# pendant2.net
KiCad netlist of a schematic drawn in EAGLE
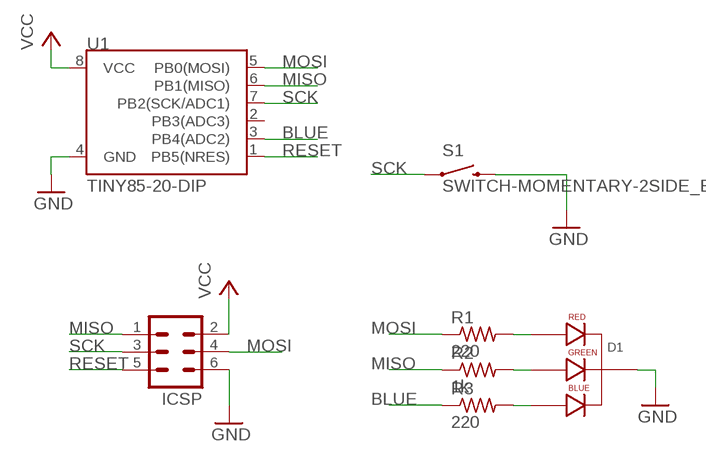
[diagram p0: schematic, sheet 1]

(export (version "E")
  (design (tool "Eeschema 10.0.6"))
  (components
    (comp (ref "D1")
      (value "LED-RGB-CC-THRUCLEAR")
      (footprint "eagle-import:LED-RGB-THRU")
      (libsource (lib "eagle-import") (part "LED-RGB-CC-THRUCLEAR"))
    )
    (comp (ref "ICSP")
      (value "MA03-2")
      (footprint "eagle-import:MA03-2")
      (libsource (lib "eagle-import") (part "MA03-2"))
    )
    (comp (ref "R1")
      (value "220")
      (footprint "eagle-import:0207_2V")
      (libsource (lib "eagle-import") (part "R-US_0207/2V"))
    )
    (comp (ref "R2")
      (value "1k")
      (footprint "eagle-import:0207_2V")
      (libsource (lib "eagle-import") (part "R-US_0207/2V"))
    )
    (comp (ref "R3")
      (value "220")
      (footprint "eagle-import:0207_2V")
      (libsource (lib "eagle-import") (part "R-US_0207/2V"))
    )
    (comp (ref "S1")
      (value "SWITCH-MOMENTARY-2SIDE_EZ")
      (footprint "eagle-import:TACTILE-PTH-SIDEEZ")
      (libsource (lib "eagle-import") (part "SWITCH-MOMENTARY-2SIDE_EZ"))
    )
    (comp (ref "U1")
      (value "TINY85-20-DIP")
      (footprint "eagle-import:DIP08")
      (libsource (lib "eagle-import") (part "ATTINY45TINY85-20-DIP"))
    )
  )
  (nets
    (net (code "1") (name "/BLUE") (class "Default")
      (node (ref "R3") (pin "1") (pinfunction "1_1") (pintype "passive"))
      (node (ref "U1") (pin "3") (pinfunction "PB4(ADC2)_3") (pintype "bidirectional"))
    )
    (net (code "2") (name "/MISO") (class "Default")
      (node (ref "ICSP") (pin "1") (pinfunction "1_1") (pintype "passive"))
      (node (ref "R2") (pin "1") (pinfunction "1_1") (pintype "passive"))
      (node (ref "U1") (pin "6") (pinfunction "PB1(MISO)_6") (pintype "bidirectional"))
    )
    (net (code "3") (name "/MOSI") (class "Default")
      (node (ref "ICSP") (pin "4") (pinfunction "4_4") (pintype "passive"))
      (node (ref "R1") (pin "1") (pinfunction "1_1") (pintype "passive"))
      (node (ref "U1") (pin "5") (pinfunction "PB0(MOSI)_5") (pintype "bidirectional"))
    )
    (net (code "4") (name "/RESET") (class "Default")
      (node (ref "ICSP") (pin "5") (pinfunction "5_5") (pintype "passive"))
      (node (ref "U1") (pin "1") (pinfunction "PB5(NRES)_1") (pintype "bidirectional"))
    )
    (net (code "5") (name "/SCK") (class "Default")
      (node (ref "ICSP") (pin "3") (pinfunction "3_3") (pintype "passive"))
      (node (ref "S1") (pin "1") (pinfunction "1_1") (pintype "passive"))
      (node (ref "U1") (pin "7") (pinfunction "PB2(SCK/ADC1)_7") (pintype "bidirectional"))
    )
    (net (code "6") (name "GND") (class "Default")
      (node (ref "D1") (pin "2") (pinfunction "CATHODE_2") (pintype "bidirectional"))
      (node (ref "ICSP") (pin "6") (pinfunction "6_6") (pintype "passive"))
      (node (ref "S1") (pin "2") (pinfunction "2_2") (pintype "passive"))
      (node (ref "U1") (pin "4") (pinfunction "GND_4") (pintype "bidirectional"))
    )
    (net (code "7") (name "Net-(D1-BLUE_CATHODE)") (class "Default")
      (node (ref "D1") (pin "4") (pinfunction "BLUE_CATHODE_4") (pintype "bidirectional"))
      (node (ref "R3") (pin "2") (pinfunction "2_2") (pintype "passive"))
    )
    (net (code "8") (name "Net-(D1-GREEN_CATHODE)") (class "Default")
      (node (ref "D1") (pin "3") (pinfunction "GREEN_CATHODE_3") (pintype "bidirectional"))
      (node (ref "R2") (pin "2") (pinfunction "2_2") (pintype "passive"))
    )
    (net (code "9") (name "Net-(D1-RED_CATHODE)") (class "Default")
      (node (ref "D1") (pin "1") (pinfunction "RED_CATHODE_1") (pintype "bidirectional"))
      (node (ref "R1") (pin "2") (pinfunction "2_2") (pintype "passive"))
    )
    (net (code "10") (name "VCC") (class "Default")
      (node (ref "ICSP") (pin "2") (pinfunction "2_2") (pintype "passive"))
      (node (ref "U1") (pin "8") (pinfunction "VCC_8") (pintype "bidirectional"))
    )
    (net (code "11") (name "unconnected-(U1-PB3(ADC3)-Pad2)") (class "Default")
      (node (ref "U1") (pin "2") (pinfunction "PB3(ADC3)_2") (pintype "bidirectional"))
    )
  )
)
